# axiom_beta_plugin_module_3xmDP_v1_2_r1_4.net
KiCad netlist of a schematic drawn in EAGLE
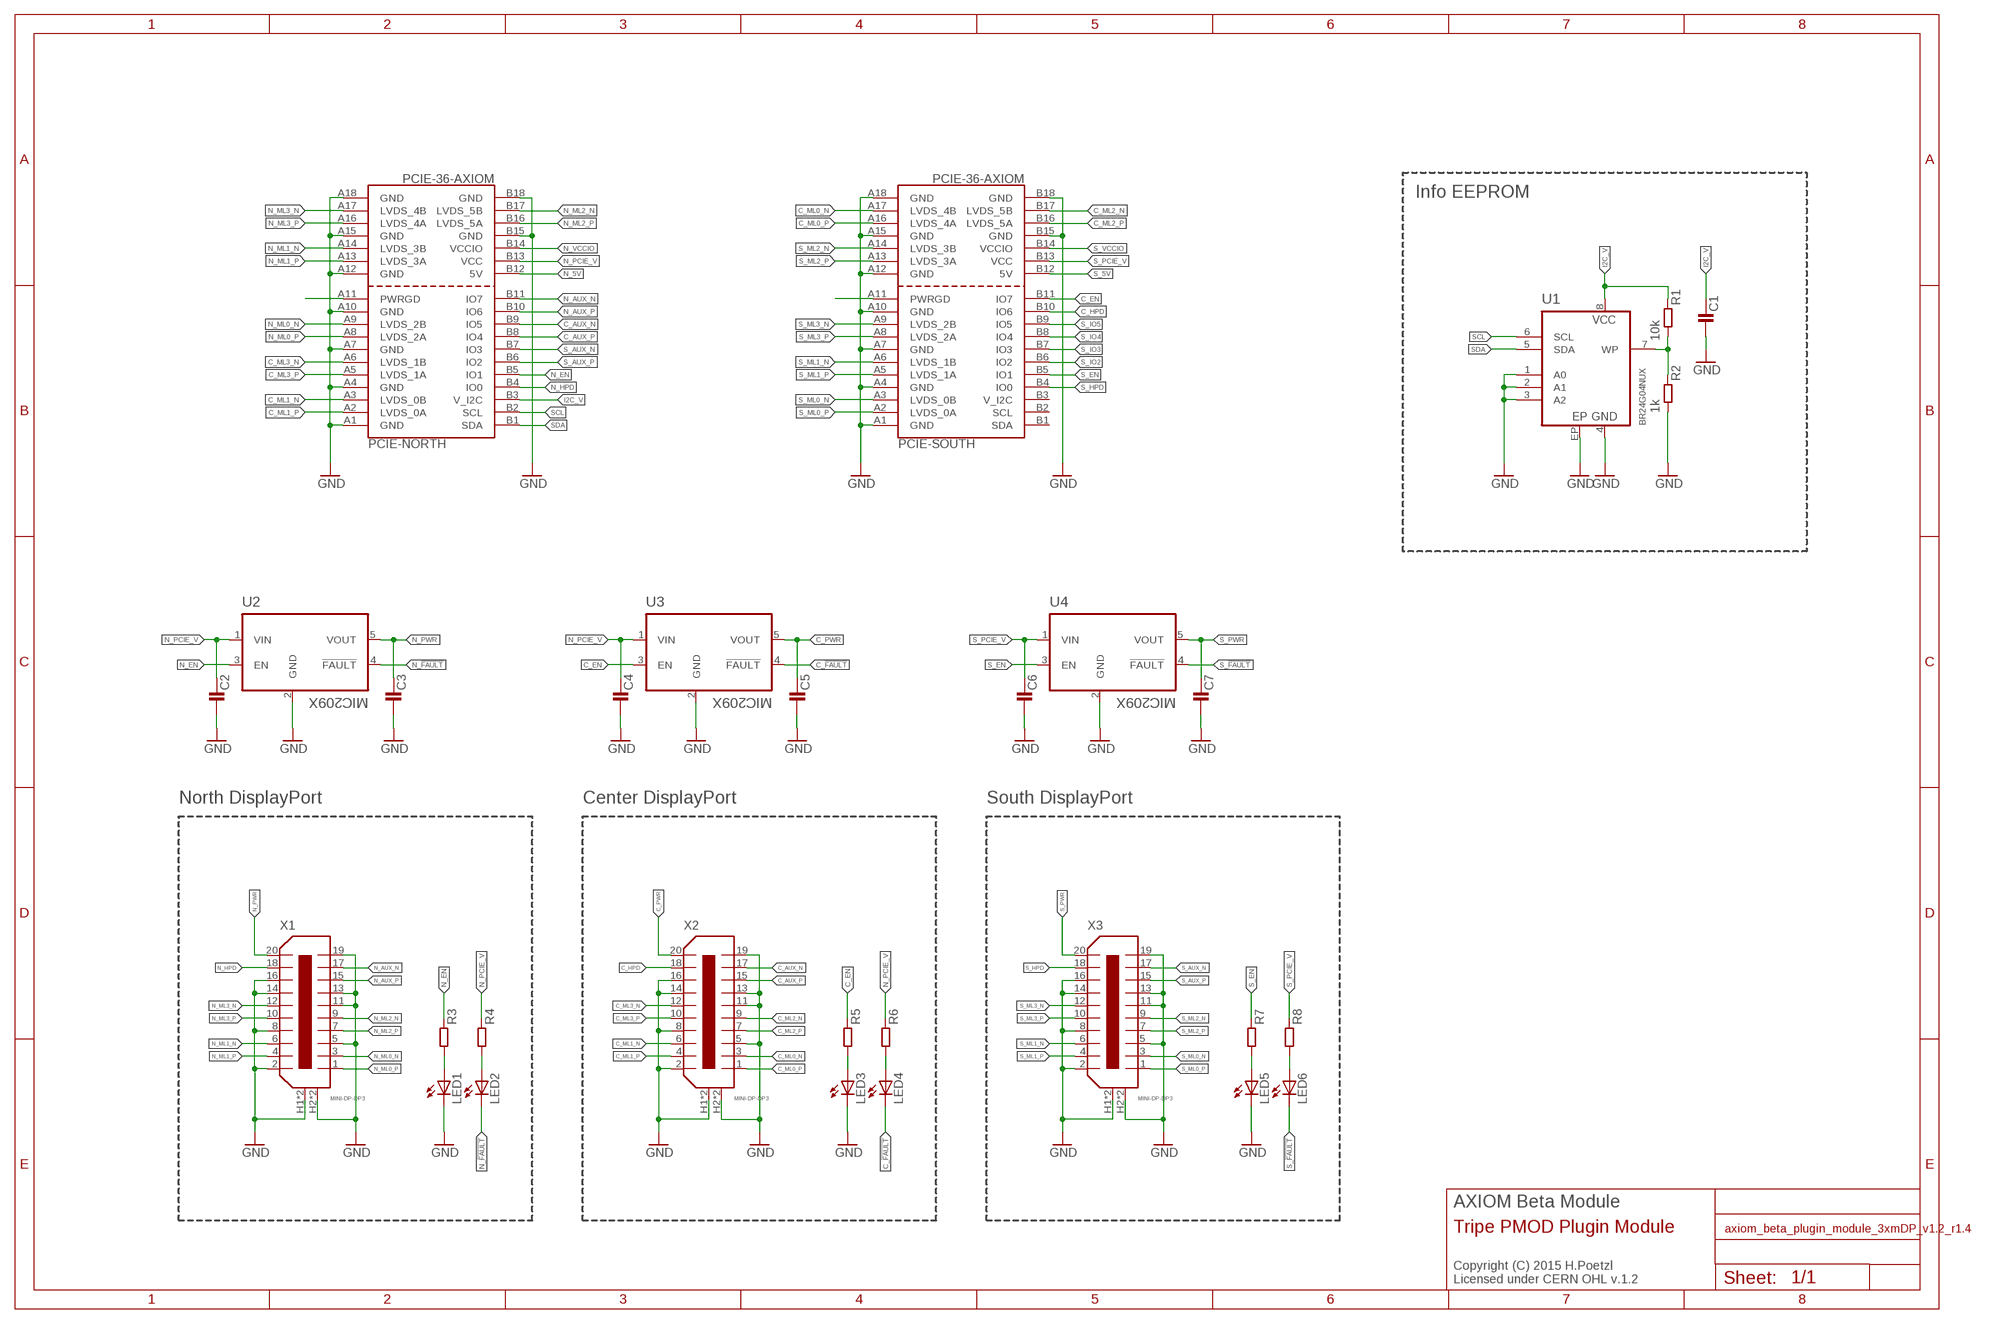
[diagram p0: schematic, sheet 1]

(export (version "E")
  (design (tool "Eeschema 10.0.6"))
  (components
    (comp (ref "C1")
      (value "C0402-B")
      (footprint "eagle-import:0402-B")
      (libsource (lib "eagle-import") (part "C0402-B"))
    )
    (comp (ref "C2")
      (value "C0603-B")
      (footprint "eagle-import:0603-B")
      (libsource (lib "eagle-import") (part "C0603-B"))
    )
    (comp (ref "C3")
      (value "C0603-B")
      (footprint "eagle-import:0603-B")
      (libsource (lib "eagle-import") (part "C0603-B"))
    )
    (comp (ref "C4")
      (value "C0603-B")
      (footprint "eagle-import:0603-B")
      (libsource (lib "eagle-import") (part "C0603-B"))
    )
    (comp (ref "C5")
      (value "C0603-B")
      (footprint "eagle-import:0603-B")
      (libsource (lib "eagle-import") (part "C0603-B"))
    )
    (comp (ref "C6")
      (value "C0603-B")
      (footprint "eagle-import:0603-B")
      (libsource (lib "eagle-import") (part "C0603-B"))
    )
    (comp (ref "C7")
      (value "C0603-B")
      (footprint "eagle-import:0603-B")
      (libsource (lib "eagle-import") (part "C0603-B"))
    )
    (comp (ref "LED1")
      (value "LEDCHIPLED_0603")
      (footprint "eagle-import:CHIPLED_0603")
      (libsource (lib "eagle-import") (part "LEDCHIPLED_0603"))
    )
    (comp (ref "LED2")
      (value "LEDCHIPLED_0603")
      (footprint "eagle-import:CHIPLED_0603")
      (libsource (lib "eagle-import") (part "LEDCHIPLED_0603"))
    )
    (comp (ref "LED3")
      (value "LEDCHIPLED_0603")
      (footprint "eagle-import:CHIPLED_0603")
      (libsource (lib "eagle-import") (part "LEDCHIPLED_0603"))
    )
    (comp (ref "LED4")
      (value "LEDCHIPLED_0603")
      (footprint "eagle-import:CHIPLED_0603")
      (libsource (lib "eagle-import") (part "LEDCHIPLED_0603"))
    )
    (comp (ref "LED5")
      (value "LEDCHIPLED_0603")
      (footprint "eagle-import:CHIPLED_0603")
      (libsource (lib "eagle-import") (part "LEDCHIPLED_0603"))
    )
    (comp (ref "LED6")
      (value "LEDCHIPLED_0603")
      (footprint "eagle-import:CHIPLED_0603")
      (libsource (lib "eagle-import") (part "LEDCHIPLED_0603"))
    )
    (comp (ref "PCIE-NORTH")
      (value "PCIE-36-AXIOM")
      (footprint "eagle-import:PCIE-36-AXIOM")
      (libsource (lib "eagle-import") (part "PCIE-36-AXIOM"))
    )
    (comp (ref "PCIE-SOUTH")
      (value "PCIE-36-AXIOM")
      (footprint "eagle-import:PCIE-36-AXIOM")
      (libsource (lib "eagle-import") (part "PCIE-36-AXIOM"))
    )
    (comp (ref "R1")
      (value "10k")
      (footprint "eagle-import:0402-B")
      (libsource (lib "eagle-import") (part "R0402-B"))
    )
    (comp (ref "R2")
      (value "1k")
      (footprint "eagle-import:0402-B")
      (libsource (lib "eagle-import") (part "R0402-B"))
    )
    (comp (ref "R3")
      (value "R0402-B")
      (footprint "eagle-import:0402-B")
      (libsource (lib "eagle-import") (part "R0402-B"))
    )
    (comp (ref "R4")
      (value "R0402-B")
      (footprint "eagle-import:0402-B")
      (libsource (lib "eagle-import") (part "R0402-B"))
    )
    (comp (ref "R5")
      (value "R0402-B")
      (footprint "eagle-import:0402-B")
      (libsource (lib "eagle-import") (part "R0402-B"))
    )
    (comp (ref "R6")
      (value "R0402-B")
      (footprint "eagle-import:0402-B")
      (libsource (lib "eagle-import") (part "R0402-B"))
    )
    (comp (ref "R7")
      (value "R0402-B")
      (footprint "eagle-import:0402-B")
      (libsource (lib "eagle-import") (part "R0402-B"))
    )
    (comp (ref "R8")
      (value "R0402-B")
      (footprint "eagle-import:0402-B")
      (libsource (lib "eagle-import") (part "R0402-B"))
    )
    (comp (ref "U1")
      (value "BR24G04NUX")
      (footprint "eagle-import:DFN200X300X100-9N")
      (libsource (lib "eagle-import") (part "BR24G04NUX"))
    )
    (comp (ref "U2")
      (value "MIC209X")
      (footprint "eagle-import:SOT95P280X145-5N")
      (fields (field (name "MPN") "MIC2090-1YM5TR"))
      (libsource (lib "eagle-import") (part "MIC209X"))
    )
    (comp (ref "U3")
      (value "MIC209X")
      (footprint "eagle-import:SOT95P280X145-5N")
      (fields (field (name "MPN") "MIC2090-1YM5TR"))
      (libsource (lib "eagle-import") (part "MIC209X"))
    )
    (comp (ref "U4")
      (value "MIC209X")
      (footprint "eagle-import:SOT95P280X145-5N")
      (fields (field (name "MPN") "MIC2090-1YM5TR"))
      (libsource (lib "eagle-import") (part "MIC209X"))
    )
    (comp (ref "X1")
      (value "MINI-DP-DP3")
      (footprint "eagle-import:JAE-DP3")
      (libsource (lib "eagle-import") (part "MINI-DP-DP3"))
    )
    (comp (ref "X2")
      (value "MINI-DP-DP3")
      (footprint "eagle-import:JAE-DP3")
      (libsource (lib "eagle-import") (part "MINI-DP-DP3"))
    )
    (comp (ref "X3")
      (value "MINI-DP-DP3")
      (footprint "eagle-import:JAE-DP3")
      (libsource (lib "eagle-import") (part "MINI-DP-DP3"))
    )
  )
  (nets
    (net (code "1") (name "/C_~{FAULT}") (class "Default")
      (node (ref "LED4") (pin "C") (pinfunction "C_C") (pintype "passive"))
      (node (ref "U3") (pin "4") (pinfunction "~{FAULT}_4") (pintype "output"))
    )
    (net (code "2") (name "/N_~{FAULT}") (class "Default")
      (node (ref "LED2") (pin "C") (pinfunction "C_C") (pintype "passive"))
      (node (ref "U2") (pin "4") (pinfunction "~{FAULT}_4") (pintype "output"))
    )
    (net (code "3") (name "/S_~{FAULT}") (class "Default")
      (node (ref "LED6") (pin "C") (pinfunction "C_C") (pintype "passive"))
      (node (ref "U4") (pin "4") (pinfunction "~{FAULT}_4") (pintype "output"))
    )
    (net (code "4") (name "C_AUX_N") (class "Default")
      (node (ref "PCIE-NORTH") (pin "B9") (pinfunction "IO5_B9") (pintype "passive"))
      (node (ref "X2") (pin "17") (pinfunction "17_17") (pintype "passive"))
    )
    (net (code "5") (name "C_AUX_P") (class "Default")
      (node (ref "PCIE-NORTH") (pin "B8") (pinfunction "IO4_B8") (pintype "passive"))
      (node (ref "X2") (pin "15") (pinfunction "15_15") (pintype "passive"))
    )
    (net (code "6") (name "C_EN") (class "Default")
      (node (ref "PCIE-SOUTH") (pin "B11") (pinfunction "IO7_B11") (pintype "passive"))
      (node (ref "R5") (pin "1") (pinfunction "1_1") (pintype "passive"))
      (node (ref "U3") (pin "3") (pinfunction "EN_3") (pintype "input"))
    )
    (net (code "7") (name "C_HPD") (class "Default")
      (node (ref "PCIE-SOUTH") (pin "B10") (pinfunction "IO6_B10") (pintype "passive"))
      (node (ref "X2") (pin "18") (pinfunction "18_18") (pintype "passive"))
    )
    (net (code "8") (name "C_ML0_N") (class "Default")
      (node (ref "PCIE-SOUTH") (pin "A17") (pinfunction "LVDS_4B_A17") (pintype "passive"))
      (node (ref "X2") (pin "3") (pinfunction "3_3") (pintype "passive"))
    )
    (net (code "9") (name "C_ML0_P") (class "Default")
      (node (ref "PCIE-SOUTH") (pin "A16") (pinfunction "LVDS_4A_A16") (pintype "passive"))
      (node (ref "X2") (pin "1") (pinfunction "1_1") (pintype "passive"))
    )
    (net (code "10") (name "C_ML1_N") (class "Default")
      (node (ref "PCIE-NORTH") (pin "A3") (pinfunction "LVDS_0B_A3") (pintype "passive"))
      (node (ref "X2") (pin "6") (pinfunction "6_6") (pintype "passive"))
    )
    (net (code "11") (name "C_ML1_P") (class "Default")
      (node (ref "PCIE-NORTH") (pin "A2") (pinfunction "LVDS_0A_A2") (pintype "passive"))
      (node (ref "X2") (pin "4") (pinfunction "4_4") (pintype "passive"))
    )
    (net (code "12") (name "C_ML2_N") (class "Default")
      (node (ref "PCIE-SOUTH") (pin "B17") (pinfunction "LVDS_5B_B17") (pintype "passive"))
      (node (ref "X2") (pin "9") (pinfunction "9_9") (pintype "passive"))
    )
    (net (code "13") (name "C_ML2_P") (class "Default")
      (node (ref "PCIE-SOUTH") (pin "B16") (pinfunction "LVDS_5A_B16") (pintype "passive"))
      (node (ref "X2") (pin "7") (pinfunction "7_7") (pintype "passive"))
    )
    (net (code "14") (name "C_ML3_N") (class "Default")
      (node (ref "PCIE-NORTH") (pin "A6") (pinfunction "LVDS_1B_A6") (pintype "passive"))
      (node (ref "X2") (pin "12") (pinfunction "12_12") (pintype "passive"))
    )
    (net (code "15") (name "C_ML3_P") (class "Default")
      (node (ref "PCIE-NORTH") (pin "A5") (pinfunction "LVDS_1A_A5") (pintype "passive"))
      (node (ref "X2") (pin "10") (pinfunction "10_10") (pintype "passive"))
    )
    (net (code "16") (name "C_PWR") (class "Default")
      (node (ref "C5") (pin "1") (pinfunction "1_1") (pintype "passive"))
      (node (ref "U3") (pin "5") (pinfunction "VOUT_5") (pintype "output"))
      (node (ref "X2") (pin "20") (pinfunction "20_20") (pintype "passive"))
    )
    (net (code "17") (name "GND") (class "Default")
      (node (ref "C1") (pin "2") (pinfunction "2_2") (pintype "passive"))
      (node (ref "C2") (pin "2") (pinfunction "2_2") (pintype "passive"))
      (node (ref "C3") (pin "2") (pinfunction "2_2") (pintype "passive"))
      (node (ref "C4") (pin "2") (pinfunction "2_2") (pintype "passive"))
      (node (ref "C5") (pin "2") (pinfunction "2_2") (pintype "passive"))
      (node (ref "C6") (pin "2") (pinfunction "2_2") (pintype "passive"))
      (node (ref "C7") (pin "2") (pinfunction "2_2") (pintype "passive"))
      (node (ref "LED1") (pin "C") (pinfunction "C_C") (pintype "passive"))
      (node (ref "LED3") (pin "C") (pinfunction "C_C") (pintype "passive"))
      (node (ref "LED5") (pin "C") (pinfunction "C_C") (pintype "passive"))
      (node (ref "PCIE-NORTH") (pin "A1") (pinfunction "GND_A1") (pintype "passive"))
      (node (ref "PCIE-NORTH") (pin "A10") (pinfunction "GND_A10") (pintype "passive"))
      (node (ref "PCIE-NORTH") (pin "A12") (pinfunction "GND_A12") (pintype "passive"))
      (node (ref "PCIE-NORTH") (pin "A15") (pinfunction "GND_A15") (pintype "passive"))
      (node (ref "PCIE-NORTH") (pin "A18") (pinfunction "GND_A18") (pintype "passive"))
      (node (ref "PCIE-NORTH") (pin "A4") (pinfunction "GND_A4") (pintype "passive"))
      (node (ref "PCIE-NORTH") (pin "A7") (pinfunction "GND_A7") (pintype "passive"))
      (node (ref "PCIE-NORTH") (pin "B15") (pinfunction "GND_B15") (pintype "passive"))
      (node (ref "PCIE-NORTH") (pin "B18") (pinfunction "GND_B18") (pintype "passive"))
      (node (ref "PCIE-SOUTH") (pin "A1") (pinfunction "GND_A1") (pintype "passive"))
      (node (ref "PCIE-SOUTH") (pin "A10") (pinfunction "GND_A10") (pintype "passive"))
      (node (ref "PCIE-SOUTH") (pin "A12") (pinfunction "GND_A12") (pintype "passive"))
      (node (ref "PCIE-SOUTH") (pin "A15") (pinfunction "GND_A15") (pintype "passive"))
      (node (ref "PCIE-SOUTH") (pin "A18") (pinfunction "GND_A18") (pintype "passive"))
      (node (ref "PCIE-SOUTH") (pin "A4") (pinfunction "GND_A4") (pintype "passive"))
      (node (ref "PCIE-SOUTH") (pin "A7") (pinfunction "GND_A7") (pintype "passive"))
      (node (ref "PCIE-SOUTH") (pin "B15") (pinfunction "GND_B15") (pintype "passive"))
      (node (ref "PCIE-SOUTH") (pin "B18") (pinfunction "GND_B18") (pintype "passive"))
      (node (ref "R2") (pin "2") (pinfunction "2_2") (pintype "passive"))
      (node (ref "U1") (pin "1") (pinfunction "A0_1") (pintype "input"))
      (node (ref "U1") (pin "2") (pinfunction "A1_2") (pintype "input"))
      (node (ref "U1") (pin "3") (pinfunction "A2_3") (pintype "input"))
      (node (ref "U1") (pin "4") (pinfunction "GND_4") (pintype "passive"))
      (node (ref "U1") (pin "EP") (pinfunction "EP_EP") (pintype "passive"))
      (node (ref "U2") (pin "2") (pinfunction "GND_2") (pintype "passive"))
      (node (ref "U3") (pin "2") (pinfunction "GND_2") (pintype "passive"))
      (node (ref "U4") (pin "2") (pinfunction "GND_2") (pintype "passive"))
      (node (ref "X1") (pin "11") (pinfunction "11_11") (pintype "passive"))
      (node (ref "X1") (pin "13") (pinfunction "13_13") (pintype "passive"))
      (node (ref "X1") (pin "14") (pinfunction "14_14") (pintype "passive"))
      (node (ref "X1") (pin "16") (pinfunction "16_16") (pintype "passive"))
      (node (ref "X1") (pin "19") (pinfunction "19_19") (pintype "passive"))
      (node (ref "X1") (pin "2") (pinfunction "2_2") (pintype "passive"))
      (node (ref "X1") (pin "5") (pinfunction "5_5") (pintype "passive"))
      (node (ref "X1") (pin "8") (pinfunction "8_8") (pintype "passive"))
      (node (ref "X1") (pin "H1") (pinfunction "M_H1") (pintype "input"))
      (node (ref "X1") (pin "H2") (pinfunction "M_H2") (pintype "input"))
      (node (ref "X1") (pin "H3") (pinfunction "M_H3") (pintype "input"))
      (node (ref "X1") (pin "H4") (pinfunction "M_H4") (pintype "input"))
      (node (ref "X2") (pin "11") (pinfunction "11_11") (pintype "passive"))
      (node (ref "X2") (pin "13") (pinfunction "13_13") (pintype "passive"))
      (node (ref "X2") (pin "14") (pinfunction "14_14") (pintype "passive"))
      (node (ref "X2") (pin "16") (pinfunction "16_16") (pintype "passive"))
      (node (ref "X2") (pin "19") (pinfunction "19_19") (pintype "passive"))
      (node (ref "X2") (pin "2") (pinfunction "2_2") (pintype "passive"))
      (node (ref "X2") (pin "5") (pinfunction "5_5") (pintype "passive"))
      (node (ref "X2") (pin "8") (pinfunction "8_8") (pintype "passive"))
      (node (ref "X2") (pin "H1") (pinfunction "M_H1") (pintype "input"))
      (node (ref "X2") (pin "H2") (pinfunction "M_H2") (pintype "input"))
      (node (ref "X2") (pin "H3") (pinfunction "M_H3") (pintype "input"))
      (node (ref "X2") (pin "H4") (pinfunction "M_H4") (pintype "input"))
      (node (ref "X3") (pin "11") (pinfunction "11_11") (pintype "passive"))
      (node (ref "X3") (pin "13") (pinfunction "13_13") (pintype "passive"))
      (node (ref "X3") (pin "14") (pinfunction "14_14") (pintype "passive"))
      (node (ref "X3") (pin "16") (pinfunction "16_16") (pintype "passive"))
      (node (ref "X3") (pin "19") (pinfunction "19_19") (pintype "passive"))
      (node (ref "X3") (pin "2") (pinfunction "2_2") (pintype "passive"))
      (node (ref "X3") (pin "5") (pinfunction "5_5") (pintype "passive"))
      (node (ref "X3") (pin "8") (pinfunction "8_8") (pintype "passive"))
      (node (ref "X3") (pin "H1") (pinfunction "M_H1") (pintype "input"))
      (node (ref "X3") (pin "H2") (pinfunction "M_H2") (pintype "input"))
      (node (ref "X3") (pin "H3") (pinfunction "M_H3") (pintype "input"))
      (node (ref "X3") (pin "H4") (pinfunction "M_H4") (pintype "input"))
    )
    (net (code "18") (name "I2C_V") (class "Default")
      (node (ref "C1") (pin "1") (pinfunction "1_1") (pintype "passive"))
      (node (ref "PCIE-NORTH") (pin "B3") (pinfunction "V_I2C_B3") (pintype "passive"))
      (node (ref "R1") (pin "1") (pinfunction "1_1") (pintype "passive"))
      (node (ref "U1") (pin "8") (pinfunction "VCC_8") (pintype "power_in"))
    )
    (net (code "19") (name "N_5V") (class "Default")
      (node (ref "PCIE-NORTH") (pin "B12") (pinfunction "5V_B12") (pintype "passive"))
    )
    (net (code "20") (name "N_AUX_N") (class "Default")
      (node (ref "PCIE-NORTH") (pin "B11") (pinfunction "IO7_B11") (pintype "passive"))
      (node (ref "X1") (pin "17") (pinfunction "17_17") (pintype "passive"))
    )
    (net (code "21") (name "N_AUX_P") (class "Default")
      (node (ref "PCIE-NORTH") (pin "B10") (pinfunction "IO6_B10") (pintype "passive"))
      (node (ref "X1") (pin "15") (pinfunction "15_15") (pintype "passive"))
    )
    (net (code "22") (name "N_EN") (class "Default")
      (node (ref "PCIE-NORTH") (pin "B5") (pinfunction "IO1_B5") (pintype "passive"))
      (node (ref "R3") (pin "1") (pinfunction "1_1") (pintype "passive"))
      (node (ref "U2") (pin "3") (pinfunction "EN_3") (pintype "input"))
    )
    (net (code "23") (name "N_HPD") (class "Default")
      (node (ref "PCIE-NORTH") (pin "B4") (pinfunction "IO0_B4") (pintype "passive"))
      (node (ref "X1") (pin "18") (pinfunction "18_18") (pintype "passive"))
    )
    (net (code "24") (name "N_ML0_N") (class "Default")
      (node (ref "PCIE-NORTH") (pin "A9") (pinfunction "LVDS_2B_A9") (pintype "passive"))
      (node (ref "X1") (pin "3") (pinfunction "3_3") (pintype "passive"))
    )
    (net (code "25") (name "N_ML0_P") (class "Default")
      (node (ref "PCIE-NORTH") (pin "A8") (pinfunction "LVDS_2A_A8") (pintype "passive"))
      (node (ref "X1") (pin "1") (pinfunction "1_1") (pintype "passive"))
    )
    (net (code "26") (name "N_ML1_N") (class "Default")
      (node (ref "PCIE-NORTH") (pin "A14") (pinfunction "LVDS_3B_A14") (pintype "passive"))
      (node (ref "X1") (pin "6") (pinfunction "6_6") (pintype "passive"))
    )
    (net (code "27") (name "N_ML1_P") (class "Default")
      (node (ref "PCIE-NORTH") (pin "A13") (pinfunction "LVDS_3A_A13") (pintype "passive"))
      (node (ref "X1") (pin "4") (pinfunction "4_4") (pintype "passive"))
    )
    (net (code "28") (name "N_ML2_N") (class "Default")
      (node (ref "PCIE-NORTH") (pin "B17") (pinfunction "LVDS_5B_B17") (pintype "passive"))
      (node (ref "X1") (pin "9") (pinfunction "9_9") (pintype "passive"))
    )
    (net (code "29") (name "N_ML2_P") (class "Default")
      (node (ref "PCIE-NORTH") (pin "B16") (pinfunction "LVDS_5A_B16") (pintype "passive"))
      (node (ref "X1") (pin "7") (pinfunction "7_7") (pintype "passive"))
    )
    (net (code "30") (name "N_ML3_N") (class "Default")
      (node (ref "PCIE-NORTH") (pin "A17") (pinfunction "LVDS_4B_A17") (pintype "passive"))
      (node (ref "X1") (pin "12") (pinfunction "12_12") (pintype "passive"))
    )
    (net (code "31") (name "N_ML3_P") (class "Default")
      (node (ref "PCIE-NORTH") (pin "A16") (pinfunction "LVDS_4A_A16") (pintype "passive"))
      (node (ref "X1") (pin "10") (pinfunction "10_10") (pintype "passive"))
    )
    (net (code "32") (name "N_PCIE_V") (class "Default")
      (node (ref "C2") (pin "1") (pinfunction "1_1") (pintype "passive"))
      (node (ref "C4") (pin "1") (pinfunction "1_1") (pintype "passive"))
      (node (ref "PCIE-NORTH") (pin "B13") (pinfunction "VCC_B13") (pintype "passive"))
      (node (ref "R4") (pin "1") (pinfunction "1_1") (pintype "passive"))
      (node (ref "R6") (pin "1") (pinfunction "1_1") (pintype "passive"))
      (node (ref "U2") (pin "1") (pinfunction "VIN_1") (pintype "input"))
      (node (ref "U3") (pin "1") (pinfunction "VIN_1") (pintype "input"))
    )
    (net (code "33") (name "N_PWR") (class "Default")
      (node (ref "C3") (pin "1") (pinfunction "1_1") (pintype "passive"))
      (node (ref "U2") (pin "5") (pinfunction "VOUT_5") (pintype "output"))
      (node (ref "X1") (pin "20") (pinfunction "20_20") (pintype "passive"))
    )
    (net (code "34") (name "N_VCCIO") (class "Default")
      (node (ref "PCIE-NORTH") (pin "B14") (pinfunction "VCCIO_B14") (pintype "passive"))
    )
    (net (code "35") (name "Net-(LED1-PadA)") (class "Default")
      (node (ref "LED1") (pin "A") (pinfunction "A_A") (pintype "passive"))
      (node (ref "R3") (pin "2") (pinfunction "2_2") (pintype "passive"))
    )
    (net (code "36") (name "Net-(LED2-PadA)") (class "Default")
      (node (ref "LED2") (pin "A") (pinfunction "A_A") (pintype "passive"))
      (node (ref "R4") (pin "2") (pinfunction "2_2") (pintype "passive"))
    )
    (net (code "37") (name "Net-(LED3-PadA)") (class "Default")
      (node (ref "LED3") (pin "A") (pinfunction "A_A") (pintype "passive"))
      (node (ref "R5") (pin "2") (pinfunction "2_2") (pintype "passive"))
    )
    (net (code "38") (name "Net-(LED4-PadA)") (class "Default")
      (node (ref "LED4") (pin "A") (pinfunction "A_A") (pintype "passive"))
      (node (ref "R6") (pin "2") (pinfunction "2_2") (pintype "passive"))
    )
    (net (code "39") (name "Net-(LED5-PadA)") (class "Default")
      (node (ref "LED5") (pin "A") (pinfunction "A_A") (pintype "passive"))
      (node (ref "R7") (pin "2") (pinfunction "2_2") (pintype "passive"))
    )
    (net (code "40") (name "Net-(LED6-PadA)") (class "Default")
      (node (ref "LED6") (pin "A") (pinfunction "A_A") (pintype "passive"))
      (node (ref "R8") (pin "2") (pinfunction "2_2") (pintype "passive"))
    )
    (net (code "41") (name "Net-(U1-WP)") (class "Default")
      (node (ref "R1") (pin "2") (pinfunction "2_2") (pintype "passive"))
      (node (ref "R2") (pin "1") (pinfunction "1_1") (pintype "passive"))
      (node (ref "U1") (pin "7") (pinfunction "WP_7") (pintype "input"))
    )
    (net (code "42") (name "SCL") (class "Default")
      (node (ref "PCIE-NORTH") (pin "B2") (pinfunction "SCL_B2") (pintype "passive"))
      (node (ref "U1") (pin "6") (pinfunction "SCL_6") (pintype "input"))
    )
    (net (code "43") (name "SDA") (class "Default")
      (node (ref "PCIE-NORTH") (pin "B1") (pinfunction "SDA_B1") (pintype "passive"))
      (node (ref "U1") (pin "5") (pinfunction "SDA_5") (pintype "bidirectional"))
    )
    (net (code "44") (name "S_5V") (class "Default")
      (node (ref "PCIE-SOUTH") (pin "B12") (pinfunction "5V_B12") (pintype "passive"))
    )
    (net (code "45") (name "S_AUX_N") (class "Default")
      (node (ref "PCIE-NORTH") (pin "B7") (pinfunction "IO3_B7") (pintype "passive"))
      (node (ref "X3") (pin "17") (pinfunction "17_17") (pintype "passive"))
    )
    (net (code "46") (name "S_AUX_P") (class "Default")
      (node (ref "PCIE-NORTH") (pin "B6") (pinfunction "IO2_B6") (pintype "passive"))
      (node (ref "X3") (pin "15") (pinfunction "15_15") (pintype "passive"))
    )
    (net (code "47") (name "S_EN") (class "Default")
      (node (ref "PCIE-SOUTH") (pin "B5") (pinfunction "IO1_B5") (pintype "passive"))
      (node (ref "R7") (pin "1") (pinfunction "1_1") (pintype "passive"))
      (node (ref "U4") (pin "3") (pinfunction "EN_3") (pintype "input"))
    )
    (net (code "48") (name "S_HPD") (class "Default")
      (node (ref "PCIE-SOUTH") (pin "B4") (pinfunction "IO0_B4") (pintype "passive"))
      (node (ref "X3") (pin "18") (pinfunction "18_18") (pintype "passive"))
    )
    (net (code "49") (name "S_IO2") (class "Default")
      (node (ref "PCIE-SOUTH") (pin "B6") (pinfunction "IO2_B6") (pintype "passive"))
    )
    (net (code "50") (name "S_IO3") (class "Default")
      (node (ref "PCIE-SOUTH") (pin "B7") (pinfunction "IO3_B7") (pintype "passive"))
    )
    (net (code "51") (name "S_IO4") (class "Default")
      (node (ref "PCIE-SOUTH") (pin "B8") (pinfunction "IO4_B8") (pintype "passive"))
    )
    (net (code "52") (name "S_IO5") (class "Default")
      (node (ref "PCIE-SOUTH") (pin "B9") (pinfunction "IO5_B9") (pintype "passive"))
    )
    (net (code "53") (name "S_ML0_N") (class "Default")
      (node (ref "PCIE-SOUTH") (pin "A3") (pinfunction "LVDS_0B_A3") (pintype "passive"))
      (node (ref "X3") (pin "3") (pinfunction "3_3") (pintype "passive"))
    )
    (net (code "54") (name "S_ML0_P") (class "Default")
      (node (ref "PCIE-SOUTH") (pin "A2") (pinfunction "LVDS_0A_A2") (pintype "passive"))
      (node (ref "X3") (pin "1") (pinfunction "1_1") (pintype "passive"))
    )
    (net (code "55") (name "S_ML1_N") (class "Default")
      (node (ref "PCIE-SOUTH") (pin "A6") (pinfunction "LVDS_1B_A6") (pintype "passive"))
      (node (ref "X3") (pin "6") (pinfunction "6_6") (pintype "passive"))
    )
    (net (code "56") (name "S_ML1_P") (class "Default")
      (node (ref "PCIE-SOUTH") (pin "A5") (pinfunction "LVDS_1A_A5") (pintype "passive"))
      (node (ref "X3") (pin "4") (pinfunction "4_4") (pintype "passive"))
    )
    (net (code "57") (name "S_ML2_N") (class "Default")
      (node (ref "PCIE-SOUTH") (pin "A14") (pinfunction "LVDS_3B_A14") (pintype "passive"))
      (node (ref "X3") (pin "9") (pinfunction "9_9") (pintype "passive"))
    )
    (net (code "58") (name "S_ML2_P") (class "Default")
      (node (ref "PCIE-SOUTH") (pin "A13") (pinfunction "LVDS_3A_A13") (pintype "passive"))
      (node (ref "X3") (pin "7") (pinfunction "7_7") (pintype "passive"))
    )
    (net (code "59") (name "S_ML3_N") (class "Default")
      (node (ref "PCIE-SOUTH") (pin "A9") (pinfunction "LVDS_2B_A9") (pintype "passive"))
      (node (ref "X3") (pin "12") (pinfunction "12_12") (pintype "passive"))
    )
    (net (code "60") (name "S_ML3_P") (class "Default")
      (node (ref "PCIE-SOUTH") (pin "A8") (pinfunction "LVDS_2A_A8") (pintype "passive"))
      (node (ref "X3") (pin "10") (pinfunction "10_10") (pintype "passive"))
    )
    (net (code "61") (name "S_PCIE_V") (class "Default")
      (node (ref "C6") (pin "1") (pinfunction "1_1") (pintype "passive"))
      (node (ref "PCIE-SOUTH") (pin "B13") (pinfunction "VCC_B13") (pintype "passive"))
      (node (ref "R8") (pin "1") (pinfunction "1_1") (pintype "passive"))
      (node (ref "U4") (pin "1") (pinfunction "VIN_1") (pintype "input"))
    )
    (net (code "62") (name "S_PWR") (class "Default")
      (node (ref "C7") (pin "1") (pinfunction "1_1") (pintype "passive"))
      (node (ref "U4") (pin "5") (pinfunction "VOUT_5") (pintype "output"))
      (node (ref "X3") (pin "20") (pinfunction "20_20") (pintype "passive"))
    )
    (net (code "63") (name "S_VCCIO") (class "Default")
      (node (ref "PCIE-SOUTH") (pin "B14") (pinfunction "VCCIO_B14") (pintype "passive"))
    )
    (net (code "64") (name "unconnected-(PCIE-NORTH-PWRGD-PadA11)") (class "Default")
      (node (ref "PCIE-NORTH") (pin "A11") (pinfunction "PWRGD_A11") (pintype "passive"))
    )
    (net (code "65") (name "unconnected-(PCIE-SOUTH-PWRGD-PadA11)") (class "Default")
      (node (ref "PCIE-SOUTH") (pin "A11") (pinfunction "PWRGD_A11") (pintype "passive"))
    )
    (net (code "66") (name "unconnected-(PCIE-SOUTH-SCL-PadB2)") (class "Default")
      (node (ref "PCIE-SOUTH") (pin "B2") (pinfunction "SCL_B2") (pintype "passive"))
    )
    (net (code "67") (name "unconnected-(PCIE-SOUTH-SDA-PadB1)") (class "Default")
      (node (ref "PCIE-SOUTH") (pin "B1") (pinfunction "SDA_B1") (pintype "passive"))
    )
    (net (code "68") (name "unconnected-(PCIE-SOUTH-V_I2C-PadB3)") (class "Default")
      (node (ref "PCIE-SOUTH") (pin "B3") (pinfunction "V_I2C_B3") (pintype "passive"))
    )
  )
)
